# eBox_3G_REG.net
KiCad netlist of a schematic drawn in Altium Designer
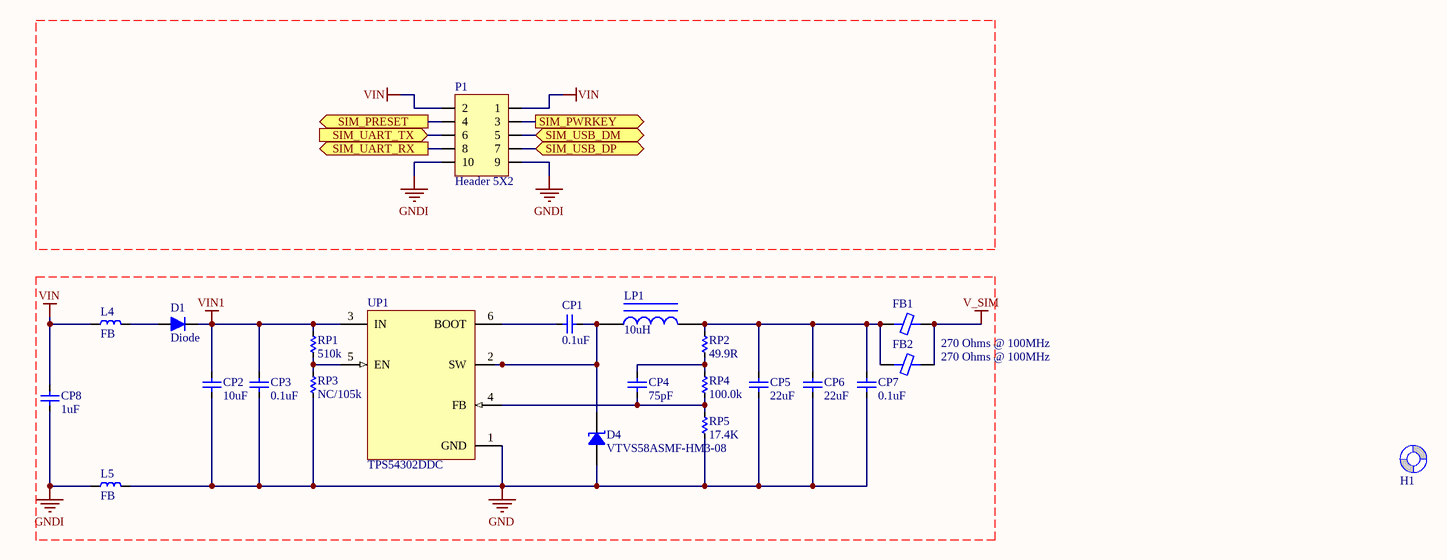
[diagram p0: eBox_3G_REG.schdoc]

(export (version "E")
  (design (tool "Eeschema 10.0.6"))
  (components
    (comp (ref "CP1")
      (value "0.1uF")
      (footprint "CC 0603")
      (description "CAP CER 0.1UF 16V X7R 0603")
      (fields
        (field (name "MANUFACTURER") "Murata Electronics")
        (field (name "MANUFACTURER PART NUMBER") "GCJ188R71C104KA01D")
      )
      (libsource (lib "car_logger_libs") (part "Capacitor NP"))
    )
    (comp (ref "CP2")
      (value "10uF")
      (footprint "CC 0805")
      (description "CAP CER 10UF 25V X5R 0805")
      (fields
        (field (name "MANUFACTURER") "Murata Electronics")
        (field (name "MANUFACTURER PART NUMBER") "GRM21BR61E106MA73L")
      )
      (libsource (lib "car_logger_libs") (part "Capacitor NP"))
    )
    (comp (ref "CP3")
      (value "0.1uF")
      (footprint "CC 0603")
      (description "CAP CER 0.1UF 16V X7R 0603")
      (fields
        (field (name "MANUFACTURER") "Murata Electronics")
        (field (name "MANUFACTURER PART NUMBER") "GCJ188R71C104KA01D")
      )
      (libsource (lib "car_logger_libs") (part "Capacitor NP"))
    )
    (comp (ref "CP4")
      (value "75pF")
      (footprint "CC 0603")
      (description "CAP CER 75PF 50V C0G/NP0 0603")
      (fields
        (field (name "MANUFACTURER") "Murata Electronics")
        (field (name "MANUFACTURER PART NUMBER") "GRM1885C1H750JA01D")
      )
      (libsource (lib "car_logger_libs") (part "Capacitor NP"))
    )
    (comp (ref "CP5")
      (value "22uF")
      (footprint "CC 0805")
      (description "CAP CER 22UF 25V X5R 0805")
      (fields
        (field (name "MANUFACTURER") "Murata Electronics")
        (field (name "MANUFACTURER PART NUMBER") "GRM21BR61E226ME44L")
      )
      (libsource (lib "car_logger_libs") (part "Capacitor NP"))
    )
    (comp (ref "CP6")
      (value "22uF")
      (footprint "CC 0805")
      (description "CAP CER 22UF 25V X5R 0805")
      (fields
        (field (name "MANUFACTURER") "Murata Electronics")
        (field (name "MANUFACTURER PART NUMBER") "GRM21BR61E226ME44L")
      )
      (libsource (lib "car_logger_libs") (part "Capacitor NP"))
    )
    (comp (ref "CP7")
      (value "0.1uF")
      (footprint "CC 0603")
      (description "CAP CER 0.1UF 16V X7R 0603")
      (fields
        (field (name "MANUFACTURER") "Murata Electronics")
        (field (name "MANUFACTURER PART NUMBER") "GCJ188R71C104KA01D")
      )
      (libsource (lib "car_logger_libs") (part "Capacitor NP"))
    )
    (comp (ref "CP8")
      (value "1uF")
      (footprint "CC 0805")
      (description "CAP CER 22UF 25V X5R 0805")
      (fields
        (field (name "MANUFACTURER") "Murata Electronics")
        (field (name "MANUFACTURER PART NUMBER") "GRM21BR61E226ME44L")
      )
      (libsource (lib "car_logger_libs") (part "Capacitor NP"))
    )
    (comp (ref "D1")
      (value "Diode")
      (footprint "DO-214AC (SMA) L")
      (description "Default Diode")
      (libsource (lib "chipfc_altium_libs") (part "Diode"))
    )
    (comp (ref "D4")
      (value "VTVS58ASMF-HM3-08")
      (footprint "SMF DO-219AB")
      (description "TVS DIODE 57.6V 98V DO219AB")
      (fields (field (name "MANUFACTURER") "Vishay Semiconductor Diodes Division"))
      (libsource (lib "Celestial Altium Library - altium_library") (part "DIODE TVS UNI"))
    )
    (comp (ref "FB1")
      (value "270 Ohms @ 100MHz")
      (footprint "L 0805 (2012)")
      (description "FERRITE BEAD 30 OHM 0805 1LN")
      (fields
        (field (name "PART NUMBER") "BLM21PG300SZ1D")
        (field (name "MANUFACTURER") "Murata Electronics")
      )
      (libsource (lib "Celestial Altium Library - altium_library") (part "Ferrite Chip"))
    )
    (comp (ref "FB2")
      (value "270 Ohms @ 100MHz")
      (footprint "L 0805 (2012)")
      (description "FERRITE BEAD 30 OHM 0805 1LN")
      (fields
        (field (name "PART NUMBER") "BLM21PG300SZ1D")
        (field (name "MANUFACTURER") "Murata Electronics")
      )
      (libsource (lib "Celestial Altium Library - altium_library") (part "Ferrite Chip"))
    )
    (comp (ref "H1")
      (value "Screw Hole")
      (footprint "SCREW/2.8M/5M")
      (libsource (lib "chipfc_altium_libs_extras") (part "Screw Hole"))
    )
    (comp (ref "L4")
      (value "FB")
      (footprint "L 0805 (2012)")
      (description "Inductor")
      (libsource (lib "chipfc_altium_libs") (part "Inductor"))
    )
    (comp (ref "L5")
      (value "FB")
      (footprint "L 0805 (2012)")
      (description "Inductor")
      (libsource (lib "chipfc_altium_libs") (part "Inductor"))
    )
    (comp (ref "LP1")
      (value "10uH")
      (footprint "IND_MWSA0518_525418")
      (description "Fixed Inductors 10uH 20% Low Profile")
      (fields
        (field (name "MANUFACTURER") "Sunlord")
        (field (name "MANUFACTURER PART NUMBER") "MWSA0518-100MT")
      )
      (libsource (lib "car_logger_libs") (part "Inductor Power"))
    )
    (comp (ref "P1")
      (value "Header 5X2")
      (footprint "HDR/Header/10/DL")
      (description "Header, 5-Pin, Dual row")
      (libsource (lib "chipfc_altium_libs") (part "Header 5X2"))
    )
    (comp (ref "RP1")
      (value "510k")
      (footprint "RR 0603")
      (description "RES SMD 510K OHM 1% 1/10W 0603")
      (fields
        (field (name "MANUFACTURER") "Panasonic Industrial Devices")
        (field (name "MANUFACTURER PART NUMBER") "ERJ-3EKF5103V")
      )
      (libsource (lib "car_logger_libs") (part "Resistors"))
    )
    (comp (ref "RP2")
      (value "49.9R")
      (footprint "RR 0603")
      (description "RES SMD 49.9 OHM 1% 1/10W 0603")
      (fields
        (field (name "MANUFACTURER") "Panasonic Industrial Devices")
        (field (name "MANUFACTURER PART NUMBER") "ERJ-3EKF49R9V")
      )
      (libsource (lib "car_logger_libs") (part "Resistors"))
    )
    (comp (ref "RP3")
      (value "NC/105k")
      (footprint "RR 0603")
      (description "RES SMD 105K OHM 1% 1/10W 0603")
      (fields
        (field (name "MANUFACTURER") "Panasonic Industrial Devices")
        (field (name "MANUFACTURER PART NUMBER") "ERJ-3EKF1053V")
      )
      (libsource (lib "car_logger_libs") (part "Resistors"))
    )
    (comp (ref "RP4")
      (value "100.0k")
      (footprint "RR 0603")
      (description "RES SMD 100K OHM 1% 1/10W 0603")
      (fields
        (field (name "MANUFACTURER") "Panasonic Industrial Devices")
        (field (name "MANUFACTURER PART NUMBER") "ERJ-3EKF1003V")
      )
      (libsource (lib "car_logger_libs") (part "Resistors"))
    )
    (comp (ref "RP5")
      (value "17.4K")
      (footprint "RR 0603")
      (description "RES SMD 17.4K OHM 1% 1/10W 0603")
      (fields
        (field (name "MANUFACTURER") "Panasonic Industrial Devices")
        (field (name "MANUFACTURER PART NUMBER") "ERJ-3EKF1742V")
      )
      (libsource (lib "car_logger_libs") (part "Resistors"))
    )
    (comp (ref "UP1")
      (value "TPS54302DDC")
      (footprint "SOT-23-6")
      (description "IC REG BUCK ADJ 3A TSOT23-6")
      (fields
        (field (name "MANUFACTURER") "Texas Instruments")
        (field (name "MANUFACTURER PART NUMBER") "TPS54302DDCR")
      )
      (libsource (lib "car_logger_libs") (part "TPS56339"))
    )
  )
  (nets
    (net (code "1") (name "/SIM_PRESET") (class "Default")
      (node (ref "P1") (pin "4") (pinfunction "4_4") (pintype "passive"))
    )
    (net (code "2") (name "/SIM_PWRKEY") (class "Default")
      (node (ref "P1") (pin "3") (pinfunction "3_3") (pintype "passive"))
    )
    (net (code "3") (name "/SIM_UART_RX") (class "Default")
      (node (ref "P1") (pin "8") (pinfunction "8_8") (pintype "passive"))
    )
    (net (code "4") (name "/SIM_UART_TX") (class "Default")
      (node (ref "P1") (pin "6") (pinfunction "6_6") (pintype "passive"))
    )
    (net (code "5") (name "/SIM_USB_DM") (class "Default")
      (node (ref "P1") (pin "5") (pinfunction "5_5") (pintype "passive"))
    )
    (net (code "6") (name "/SIM_USB_DP") (class "Default")
      (node (ref "P1") (pin "7") (pinfunction "7_7") (pintype "passive"))
    )
    (net (code "7") (name "GND") (class "Default")
      (node (ref "CP2") (pin "2") (pinfunction "2_2") (pintype "passive"))
      (node (ref "CP3") (pin "2") (pinfunction "2_2") (pintype "passive"))
      (node (ref "CP5") (pin "2") (pinfunction "2_2") (pintype "passive"))
      (node (ref "CP6") (pin "2") (pinfunction "2_2") (pintype "passive"))
      (node (ref "CP7") (pin "2") (pinfunction "2_2") (pintype "passive"))
      (node (ref "D4") (pin "1") (pinfunction "1_1") (pintype "passive"))
      (node (ref "L5") (pin "2") (pinfunction "2_2") (pintype "passive"))
      (node (ref "RP3") (pin "1") (pinfunction "1_1") (pintype "passive"))
      (node (ref "RP5") (pin "2") (pinfunction "2_2") (pintype "passive"))
      (node (ref "UP1") (pin "1") (pinfunction "GND_1") (pintype "power_in"))
    )
    (net (code "8") (name "GNDI") (class "Default")
      (node (ref "CP8") (pin "2") (pinfunction "2_2") (pintype "passive"))
      (node (ref "L5") (pin "1") (pinfunction "1_1") (pintype "passive"))
      (node (ref "P1") (pin "10") (pinfunction "10_10") (pintype "passive"))
      (node (ref "P1") (pin "9") (pinfunction "9_9") (pintype "passive"))
    )
    (net (code "9") (name "Net-(CP4-Pad1)") (class "Default")
      (node (ref "CP4") (pin "1") (pinfunction "1_1") (pintype "passive"))
      (node (ref "RP2") (pin "2") (pinfunction "2_2") (pintype "passive"))
      (node (ref "RP4") (pin "1") (pinfunction "1_1") (pintype "passive"))
    )
    (net (code "10") (name "Net-(CP5-Pad1)") (class "Default")
      (node (ref "CP5") (pin "1") (pinfunction "1_1") (pintype "passive"))
      (node (ref "CP6") (pin "1") (pinfunction "1_1") (pintype "passive"))
      (node (ref "CP7") (pin "1") (pinfunction "1_1") (pintype "passive"))
      (node (ref "FB1") (pin "1") (pinfunction "1_1") (pintype "passive"))
      (node (ref "FB2") (pin "1") (pinfunction "1_1") (pintype "passive"))
      (node (ref "LP1") (pin "2") (pinfunction "2_2") (pintype "passive"))
      (node (ref "RP2") (pin "1") (pinfunction "1_1") (pintype "passive"))
    )
    (net (code "11") (name "Net-(D1-A)") (class "Default")
      (node (ref "D1") (pin "1") (pinfunction "A_1") (pintype "passive"))
      (node (ref "L4") (pin "2") (pinfunction "2_2") (pintype "passive"))
    )
    (net (code "12") (name "Net-(UP1-BOOT)") (class "Default")
      (node (ref "CP1") (pin "1") (pinfunction "1_1") (pintype "passive"))
      (node (ref "UP1") (pin "6") (pinfunction "BOOT_6") (pintype "passive"))
    )
    (net (code "13") (name "Net-(UP1-EN)") (class "Default")
      (node (ref "RP1") (pin "1") (pinfunction "1_1") (pintype "passive"))
      (node (ref "RP3") (pin "2") (pinfunction "2_2") (pintype "passive"))
      (node (ref "UP1") (pin "5") (pinfunction "EN_5") (pintype "input"))
    )
    (net (code "14") (name "Net-(UP1-FB)") (class "Default")
      (node (ref "CP4") (pin "2") (pinfunction "2_2") (pintype "passive"))
      (node (ref "RP4") (pin "2") (pinfunction "2_2") (pintype "passive"))
      (node (ref "RP5") (pin "1") (pinfunction "1_1") (pintype "passive"))
      (node (ref "UP1") (pin "4") (pinfunction "FB_4") (pintype "input"))
    )
    (net (code "15") (name "Net-(UP1-SW)") (class "Default")
      (node (ref "CP1") (pin "2") (pinfunction "2_2") (pintype "passive"))
      (node (ref "D4") (pin "2") (pinfunction "2_2") (pintype "passive"))
      (node (ref "LP1") (pin "1") (pinfunction "1_1") (pintype "passive"))
      (node (ref "UP1") (pin "2") (pinfunction "SW_2") (pintype "power_in"))
    )
    (net (code "16") (name "VIN") (class "Default")
      (node (ref "CP8") (pin "1") (pinfunction "1_1") (pintype "passive"))
      (node (ref "L4") (pin "1") (pinfunction "1_1") (pintype "passive"))
      (node (ref "P1") (pin "1") (pinfunction "1_1") (pintype "passive"))
      (node (ref "P1") (pin "2") (pinfunction "2_2") (pintype "passive"))
    )
    (net (code "17") (name "VIN1") (class "Default")
      (node (ref "CP2") (pin "1") (pinfunction "1_1") (pintype "passive"))
      (node (ref "CP3") (pin "1") (pinfunction "1_1") (pintype "passive"))
      (node (ref "D1") (pin "2") (pinfunction "K_2") (pintype "passive"))
      (node (ref "RP1") (pin "2") (pinfunction "2_2") (pintype "passive"))
      (node (ref "UP1") (pin "3") (pinfunction "IN_3") (pintype "power_in"))
    )
    (net (code "18") (name "V_SIM") (class "Default")
      (node (ref "FB1") (pin "2") (pinfunction "2_2") (pintype "passive"))
      (node (ref "FB2") (pin "2") (pinfunction "2_2") (pintype "passive"))
    )
    (net (code "19") (name "unconnected-(H1-Screw-Pad1)") (class "Default")
      (node (ref "H1") (pin "1") (pinfunction "Screw_1") (pintype "passive"))
    )
  )
)
